# Connector.net
KiCad netlist of a schematic drawn in Altium Designer
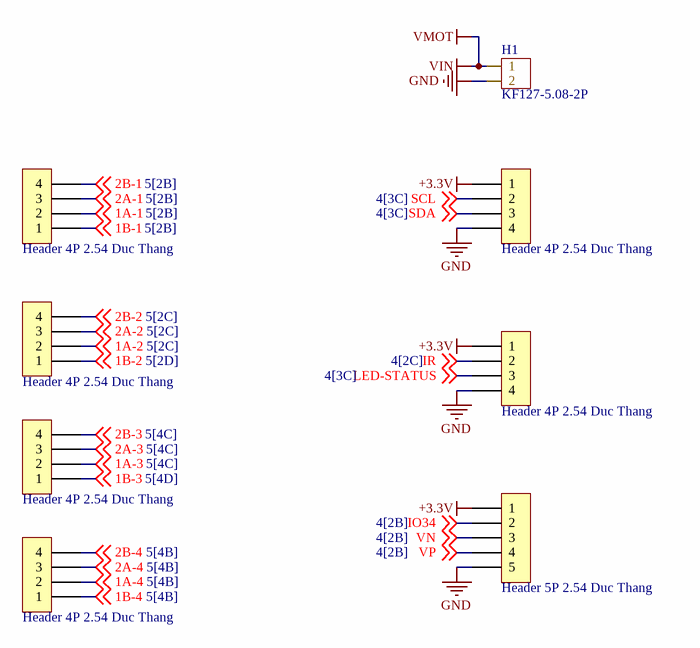
[diagram p0: Connector.SchDoc]

(export (version "E")
  (design (tool "Eeschema 10.0.6"))
  (components
    (comp (ref "H1")
      (value "KF127-5.08-2P")
      (footprint "KF127-5.08-2P")
      (fields (field (name "MANUFACTURER") "Cixi Kefa Elec") (field (name "LCSC PART #") "C474906"))
      (libsource (lib "Header") (part "KF127-5.08-2P"))
    )
    (comp (ref "H3")
      (value "Header 4P 2.54 Duc Thang")
      (footprint "XH2.54M-4")
      (description "Cắm")
      (libsource (lib "Header") (part "Header 4P 2.54 Duc Thang"))
    )
    (comp (ref "H4")
      (value "Header 4P 2.54 Duc Thang")
      (footprint "XH2.54M-4")
      (description "Cắm")
      (libsource (lib "") (part "Header 4P 2.54 Duc Thang_1"))
    )
    (comp (ref "H5")
      (value "Header 4P 2.54 Duc Thang")
      (footprint "XH2.54M-4")
      (description "Cắm")
      (libsource (lib "Header") (part "Header 4P 2.54 Duc Thang"))
    )
    (comp (ref "H6")
      (value "Header 4P 2.54 Duc Thang")
      (footprint "XH2.54M-4")
      (description "Cắm")
      (libsource (lib "") (part "Header 4P 2.54 Duc Thang_1"))
    )
    (comp (ref "H7")
      (value "Header 4P 2.54 Duc Thang")
      (footprint "XH2.54M-4")
      (description "Cắm")
      (libsource (lib "Header") (part "Header 4P 2.54 Duc Thang"))
    )
    (comp (ref "H8")
      (value "Header 5P 2.54 Duc Thang")
      (footprint "XH2.54M-5")
      (description "Cắm")
      (libsource (lib "Header") (part "Header 5P 2.54 Duc Thang"))
    )
    (comp (ref "H9")
      (value "Header 4P 2.54 Duc Thang")
      (footprint "XH2.54M-4")
      (description "Cắm")
      (libsource (lib "Header") (part "Header 4P 2.54 Duc Thang"))
    )
  )
  (nets
    (net (code "1") (name "+3.3V") (class "Default")
      (node (ref "H4") (pin "1") (pinfunction "1_1") (pintype "passive"))
      (node (ref "H6") (pin "1") (pinfunction "1_1") (pintype "passive"))
      (node (ref "H8") (pin "1") (pinfunction "1_1") (pintype "passive"))
    )
    (net (code "2") (name "1A-1") (class "Default")
      (node (ref "H3") (pin "2") (pinfunction "2_2") (pintype "passive"))
    )
    (net (code "3") (name "1A-2") (class "Default")
      (node (ref "H5") (pin "2") (pinfunction "2_2") (pintype "passive"))
    )
    (net (code "4") (name "1A-3") (class "Default")
      (node (ref "H7") (pin "2") (pinfunction "2_2") (pintype "passive"))
    )
    (net (code "5") (name "1A-4") (class "Default")
      (node (ref "H9") (pin "2") (pinfunction "2_2") (pintype "passive"))
    )
    (net (code "6") (name "1B-1") (class "Default")
      (node (ref "H3") (pin "1") (pinfunction "1_1") (pintype "passive"))
    )
    (net (code "7") (name "1B-2") (class "Default")
      (node (ref "H5") (pin "1") (pinfunction "1_1") (pintype "passive"))
    )
    (net (code "8") (name "1B-3") (class "Default")
      (node (ref "H7") (pin "1") (pinfunction "1_1") (pintype "passive"))
    )
    (net (code "9") (name "1B-4") (class "Default")
      (node (ref "H9") (pin "1") (pinfunction "1_1") (pintype "passive"))
    )
    (net (code "10") (name "2A-1") (class "Default")
      (node (ref "H3") (pin "3") (pinfunction "3_3") (pintype "passive"))
    )
    (net (code "11") (name "2A-2") (class "Default")
      (node (ref "H5") (pin "3") (pinfunction "3_3") (pintype "passive"))
    )
    (net (code "12") (name "2A-3") (class "Default")
      (node (ref "H7") (pin "3") (pinfunction "3_3") (pintype "passive"))
    )
    (net (code "13") (name "2A-4") (class "Default")
      (node (ref "H9") (pin "3") (pinfunction "3_3") (pintype "passive"))
    )
    (net (code "14") (name "2B-1") (class "Default")
      (node (ref "H3") (pin "4") (pinfunction "4_4") (pintype "passive"))
    )
    (net (code "15") (name "2B-2") (class "Default")
      (node (ref "H5") (pin "4") (pinfunction "4_4") (pintype "passive"))
    )
    (net (code "16") (name "2B-3") (class "Default")
      (node (ref "H7") (pin "4") (pinfunction "4_4") (pintype "passive"))
    )
    (net (code "17") (name "2B-4") (class "Default")
      (node (ref "H9") (pin "4") (pinfunction "4_4") (pintype "passive"))
    )
    (net (code "18") (name "GND") (class "Default")
      (node (ref "H1") (pin "2") (pinfunction "2_2") (pintype "passive"))
      (node (ref "H4") (pin "4") (pinfunction "4_4") (pintype "passive"))
      (node (ref "H6") (pin "4") (pinfunction "4_4") (pintype "passive"))
      (node (ref "H8") (pin "5") (pinfunction "5_5") (pintype "passive"))
    )
    (net (code "19") (name "IO34") (class "Default")
      (node (ref "H8") (pin "2") (pinfunction "2_2") (pintype "passive"))
    )
    (net (code "20") (name "IR") (class "Default")
      (node (ref "H6") (pin "2") (pinfunction "2_2") (pintype "passive"))
    )
    (net (code "21") (name "LED-STATUS") (class "Default")
      (node (ref "H6") (pin "3") (pinfunction "3_3") (pintype "passive"))
    )
    (net (code "22") (name "SCL") (class "Default")
      (node (ref "H4") (pin "2") (pinfunction "2_2") (pintype "passive"))
    )
    (net (code "23") (name "SDA") (class "Default")
      (node (ref "H4") (pin "3") (pinfunction "3_3") (pintype "passive"))
    )
    (net (code "24") (name "VIN") (class "Default")
      (node (ref "H1") (pin "1") (pinfunction "1_1") (pintype "passive"))
    )
    (net (code "25") (name "VN") (class "Default")
      (node (ref "H8") (pin "3") (pinfunction "3_3") (pintype "passive"))
    )
    (net (code "26") (name "VP") (class "Default")
      (node (ref "H8") (pin "4") (pinfunction "4_4") (pintype "passive"))
    )
  )
)
